# Panelizado_frentes.net
KiCad netlist of a schematic drawn in EAGLE
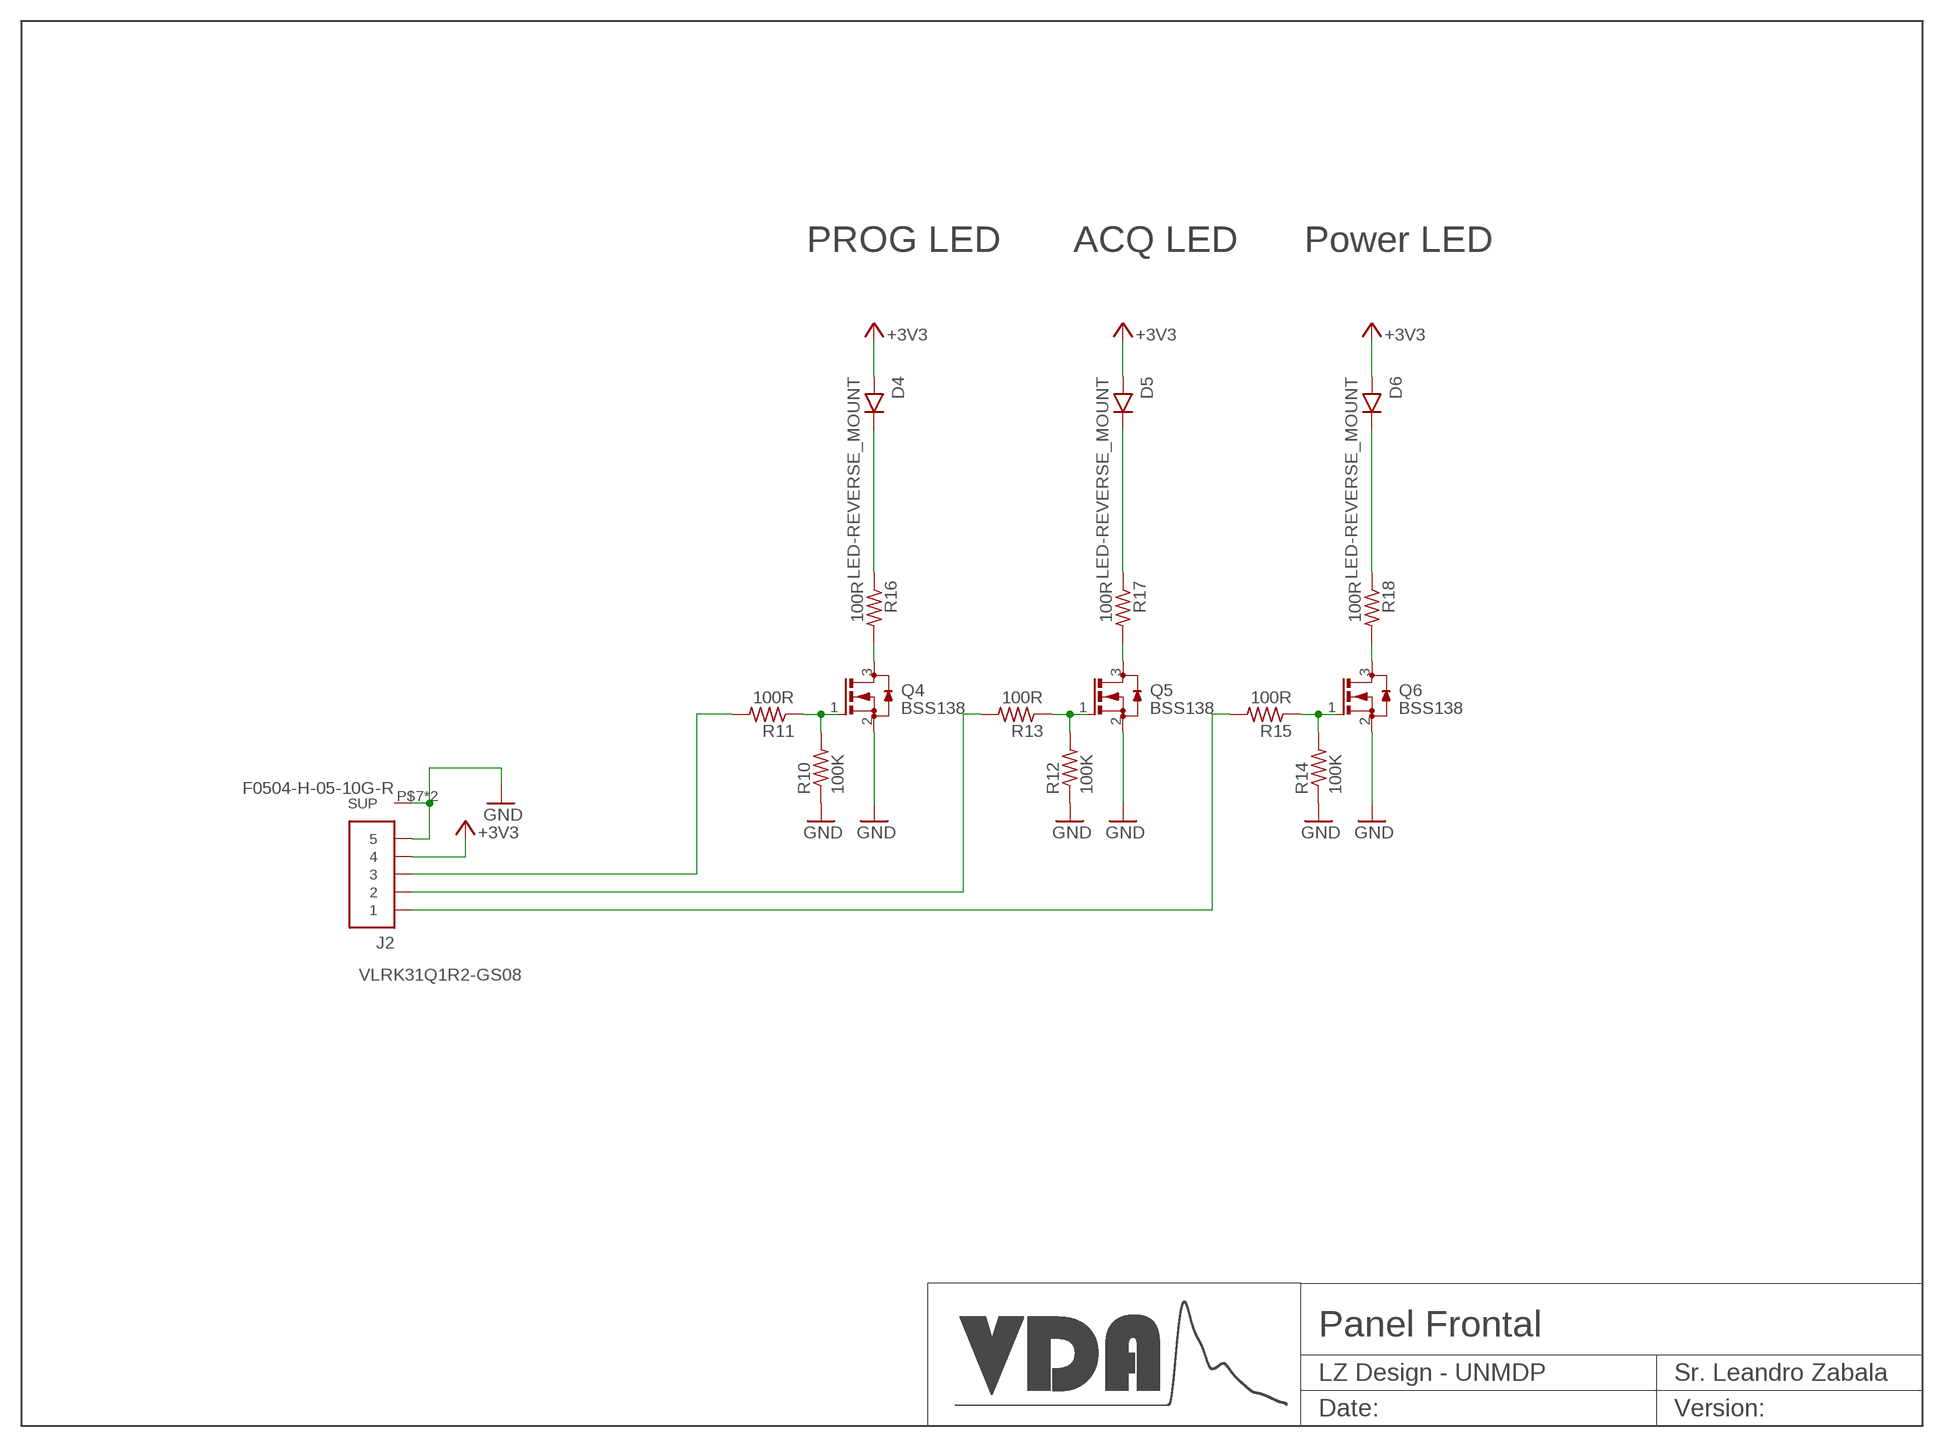
[diagram p0: schematic, sheet 1]
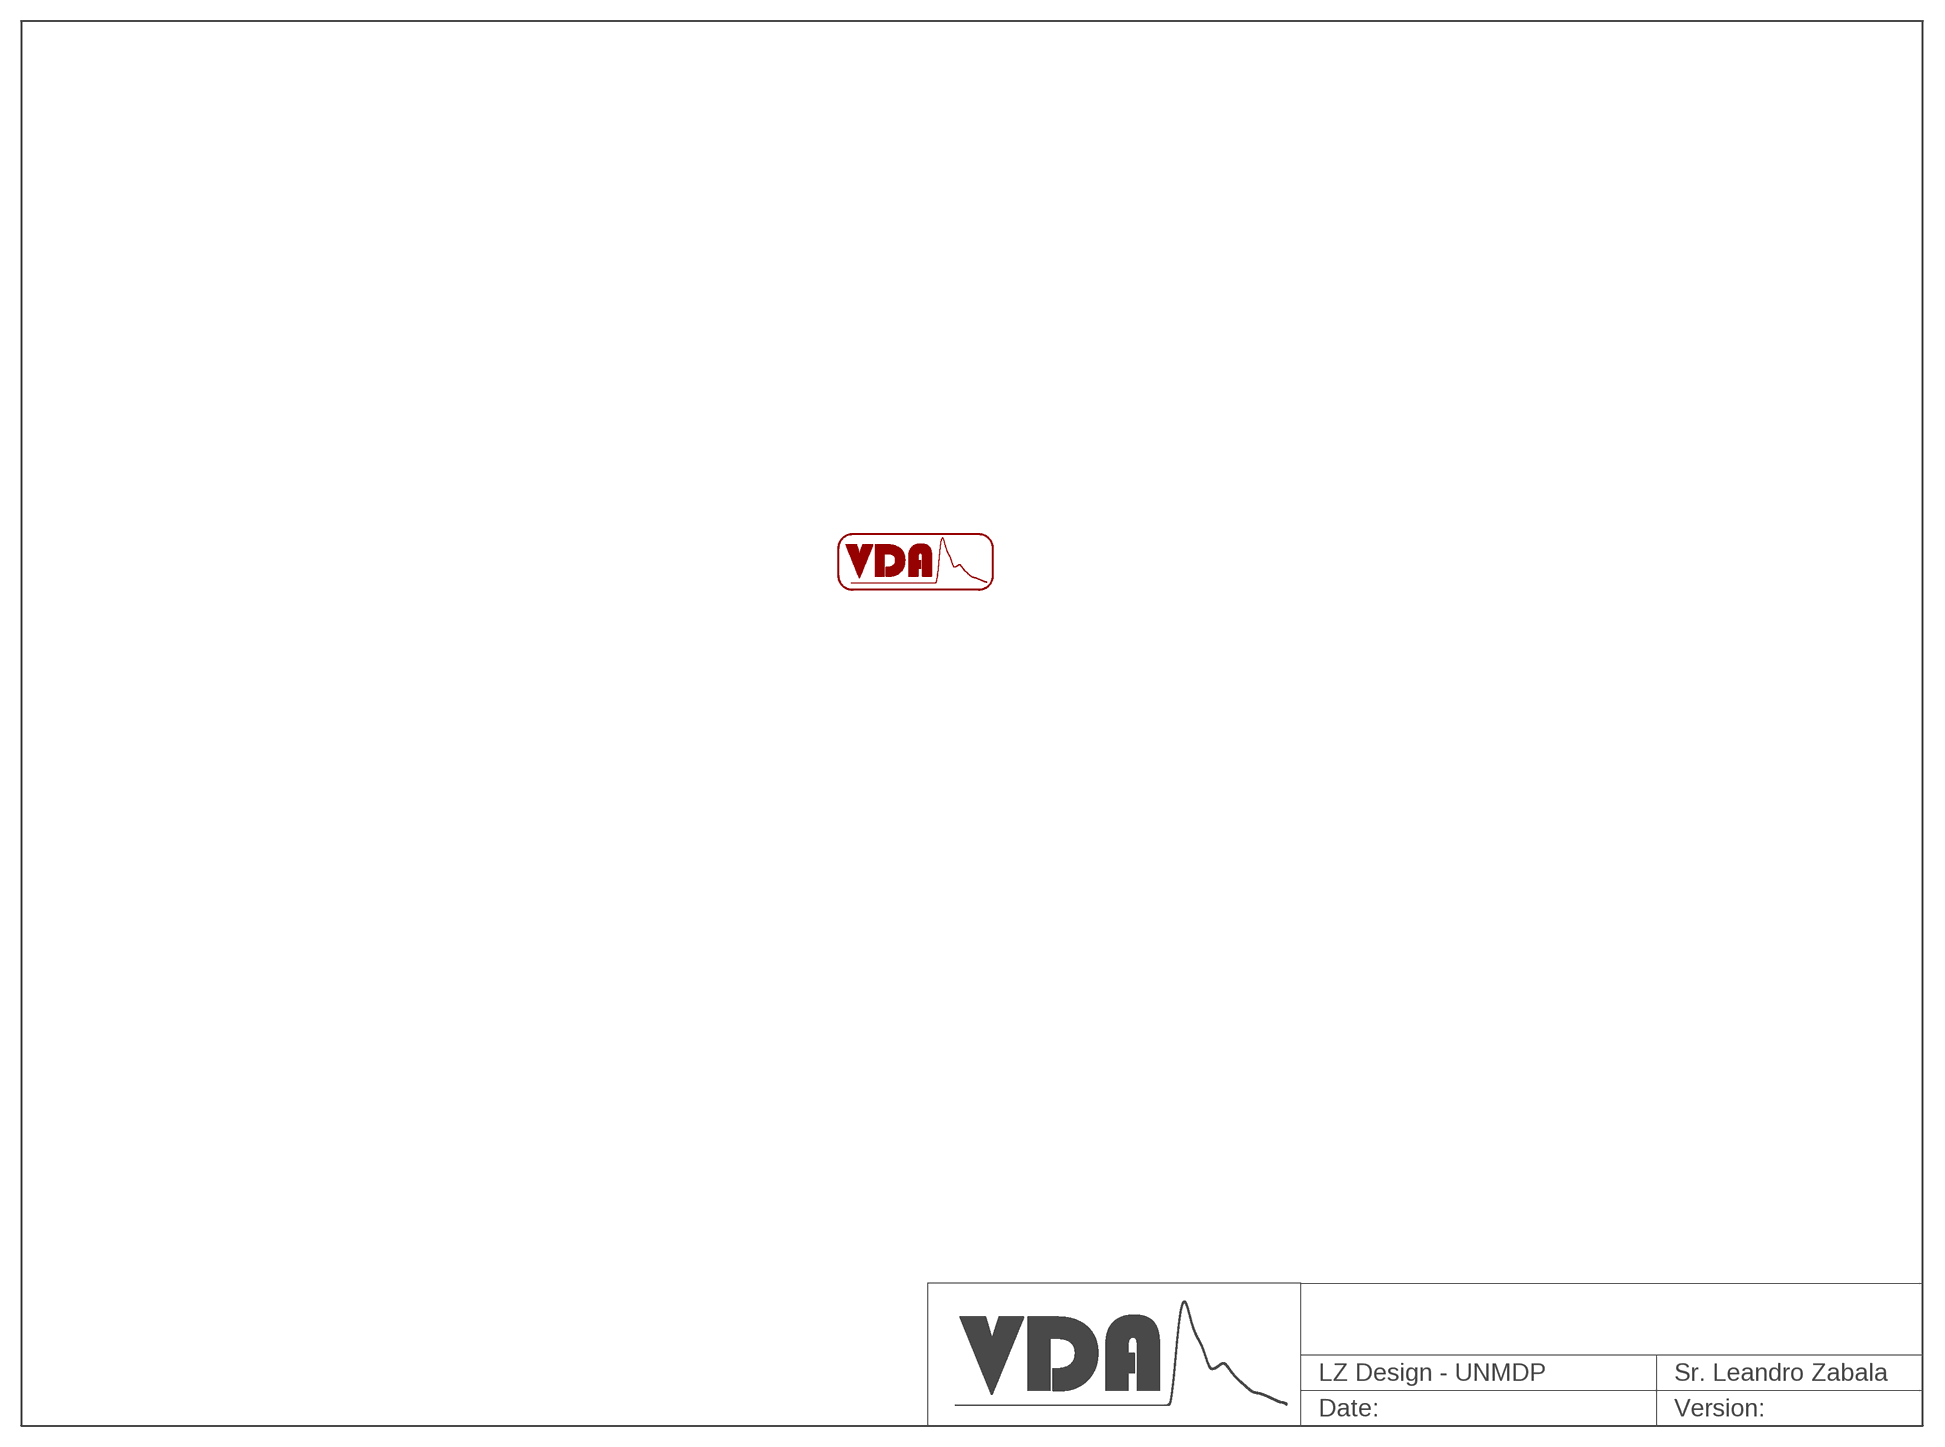
[diagram p1: schematic, sheet 2]

(export (version "E")
  (design (tool "Eeschema 10.0.6"))
  (components
    (comp (ref "U$1")
      (value "LOGO_VDA-3CM")
      (footprint "eagle-import:LOGO_VDA-3CM")
      (libsource (lib "eagle-import") (part "LOGO_VDA-3CM"))
    )
    (comp (ref "D4")
      (value "LED-REVERSE_MOUNT")
      (footprint "eagle-import:VLRK31")
      (libsource (lib "eagle-import") (part "LED-REVERSE_MOUNT"))
    )
    (comp (ref "D5")
      (value "LED-REVERSE_MOUNT")
      (footprint "eagle-import:VLRK31")
      (libsource (lib "eagle-import") (part "LED-REVERSE_MOUNT"))
    )
    (comp (ref "D6")
      (value "LED-REVERSE_MOUNT")
      (footprint "eagle-import:VLRK31")
      (libsource (lib "eagle-import") (part "LED-REVERSE_MOUNT"))
    )
    (comp (ref "J2")
      (value "F0504-H-05-10G-R")
      (footprint "eagle-import:F0504-H-05-10G-R")
      (libsource (lib "eagle-import") (part "F0504-H-05-10G-R"))
    )
    (comp (ref "Q4")
      (value "BSS138")
      (footprint "eagle-import:SOT-23")
      (libsource (lib "eagle-import") (part "N-MOS_SOT23-3"))
    )
    (comp (ref "Q5")
      (value "BSS138")
      (footprint "eagle-import:SOT-23")
      (libsource (lib "eagle-import") (part "N-MOS_SOT23-3"))
    )
    (comp (ref "Q6")
      (value "BSS138")
      (footprint "eagle-import:SOT-23")
      (libsource (lib "eagle-import") (part "N-MOS_SOT23-3"))
    )
    (comp (ref "R10")
      (value "100K")
      (footprint "eagle-import:R_0603")
      (libsource (lib "eagle-import") (part "R_0603"))
    )
    (comp (ref "R11")
      (value "100R")
      (footprint "eagle-import:R_0603")
      (libsource (lib "eagle-import") (part "R_0603"))
    )
    (comp (ref "R12")
      (value "100K")
      (footprint "eagle-import:R_0603")
      (libsource (lib "eagle-import") (part "R_0603"))
    )
    (comp (ref "R13")
      (value "100R")
      (footprint "eagle-import:R_0603")
      (libsource (lib "eagle-import") (part "R_0603"))
    )
    (comp (ref "R14")
      (value "100K")
      (footprint "eagle-import:R_0603")
      (libsource (lib "eagle-import") (part "R_0603"))
    )
    (comp (ref "R15")
      (value "100R")
      (footprint "eagle-import:R_0603")
      (libsource (lib "eagle-import") (part "R_0603"))
    )
    (comp (ref "R16")
      (value "100R")
      (footprint "eagle-import:R_0603")
      (libsource (lib "eagle-import") (part "R_0603"))
    )
    (comp (ref "R17")
      (value "100R")
      (footprint "eagle-import:R_0603")
      (libsource (lib "eagle-import") (part "R_0603"))
    )
    (comp (ref "R18")
      (value "100R")
      (footprint "eagle-import:R_0603")
      (libsource (lib "eagle-import") (part "R_0603"))
    )
  )
  (nets
    (net (code "1") (name "+3V3") (class "Default")
      (node (ref "D4") (pin "A") (pinfunction "A_A") (pintype "bidirectional"))
      (node (ref "D5") (pin "A") (pinfunction "A_A") (pintype "bidirectional"))
      (node (ref "D6") (pin "A") (pinfunction "A_A") (pintype "bidirectional"))
      (node (ref "J2") (pin "P$4") (pinfunction "4_P$4") (pintype "bidirectional"))
    )
    (net (code "2") (name "GND") (class "Default")
      (node (ref "J2") (pin "P$5") (pinfunction "5_P$5") (pintype "bidirectional"))
      (node (ref "J2") (pin "P$7") (pinfunction "SUP_P$7") (pintype "bidirectional"))
      (node (ref "J2") (pin "P$8") (pinfunction "SUP_P$8") (pintype "bidirectional"))
      (node (ref "Q4") (pin "2") (pinfunction "S_2") (pintype "passive"))
      (node (ref "Q5") (pin "2") (pinfunction "S_2") (pintype "passive"))
      (node (ref "Q6") (pin "2") (pinfunction "S_2") (pintype "passive"))
      (node (ref "R10") (pin "1") (pinfunction "1_1") (pintype "passive"))
      (node (ref "R12") (pin "1") (pinfunction "1_1") (pintype "passive"))
      (node (ref "R14") (pin "1") (pinfunction "1_1") (pintype "passive"))
    )
    (net (code "3") (name "Net-(D4-PadK)") (class "Default")
      (node (ref "D4") (pin "K") (pinfunction "K_K") (pintype "bidirectional"))
      (node (ref "R16") (pin "1") (pinfunction "1_1") (pintype "passive"))
    )
    (net (code "4") (name "Net-(D5-PadK)") (class "Default")
      (node (ref "D5") (pin "K") (pinfunction "K_K") (pintype "bidirectional"))
      (node (ref "R17") (pin "1") (pinfunction "1_1") (pintype "passive"))
    )
    (net (code "5") (name "Net-(D6-PadK)") (class "Default")
      (node (ref "D6") (pin "K") (pinfunction "K_K") (pintype "bidirectional"))
      (node (ref "R18") (pin "1") (pinfunction "1_1") (pintype "passive"))
    )
    (net (code "6") (name "Net-(J2-1)") (class "Default")
      (node (ref "J2") (pin "P$1") (pinfunction "1_P$1") (pintype "bidirectional"))
      (node (ref "R15") (pin "2") (pinfunction "2_2") (pintype "passive"))
    )
    (net (code "7") (name "Net-(J2-2)") (class "Default")
      (node (ref "J2") (pin "P$2") (pinfunction "2_P$2") (pintype "bidirectional"))
      (node (ref "R13") (pin "2") (pinfunction "2_2") (pintype "passive"))
    )
    (net (code "8") (name "Net-(J2-3)") (class "Default")
      (node (ref "J2") (pin "P$3") (pinfunction "3_P$3") (pintype "bidirectional"))
      (node (ref "R11") (pin "2") (pinfunction "2_2") (pintype "passive"))
    )
    (net (code "9") (name "Net-(Q4-D)") (class "Default")
      (node (ref "Q4") (pin "3") (pinfunction "D_3") (pintype "passive"))
      (node (ref "R16") (pin "2") (pinfunction "2_2") (pintype "passive"))
    )
    (net (code "10") (name "Net-(Q4-G)") (class "Default")
      (node (ref "Q4") (pin "1") (pinfunction "G_1") (pintype "passive"))
      (node (ref "R10") (pin "2") (pinfunction "2_2") (pintype "passive"))
      (node (ref "R11") (pin "1") (pinfunction "1_1") (pintype "passive"))
    )
    (net (code "11") (name "Net-(Q5-D)") (class "Default")
      (node (ref "Q5") (pin "3") (pinfunction "D_3") (pintype "passive"))
      (node (ref "R17") (pin "2") (pinfunction "2_2") (pintype "passive"))
    )
    (net (code "12") (name "Net-(Q5-G)") (class "Default")
      (node (ref "Q5") (pin "1") (pinfunction "G_1") (pintype "passive"))
      (node (ref "R12") (pin "2") (pinfunction "2_2") (pintype "passive"))
      (node (ref "R13") (pin "1") (pinfunction "1_1") (pintype "passive"))
    )
    (net (code "13") (name "Net-(Q6-D)") (class "Default")
      (node (ref "Q6") (pin "3") (pinfunction "D_3") (pintype "passive"))
      (node (ref "R18") (pin "2") (pinfunction "2_2") (pintype "passive"))
    )
    (net (code "14") (name "Net-(Q6-G)") (class "Default")
      (node (ref "Q6") (pin "1") (pinfunction "G_1") (pintype "passive"))
      (node (ref "R14") (pin "2") (pinfunction "2_2") (pintype "passive"))
      (node (ref "R15") (pin "1") (pinfunction "1_1") (pintype "passive"))
    )
  )
)
